# EbookReader_Schematic.net
KiCad netlist of a schematic drawn in EAGLE
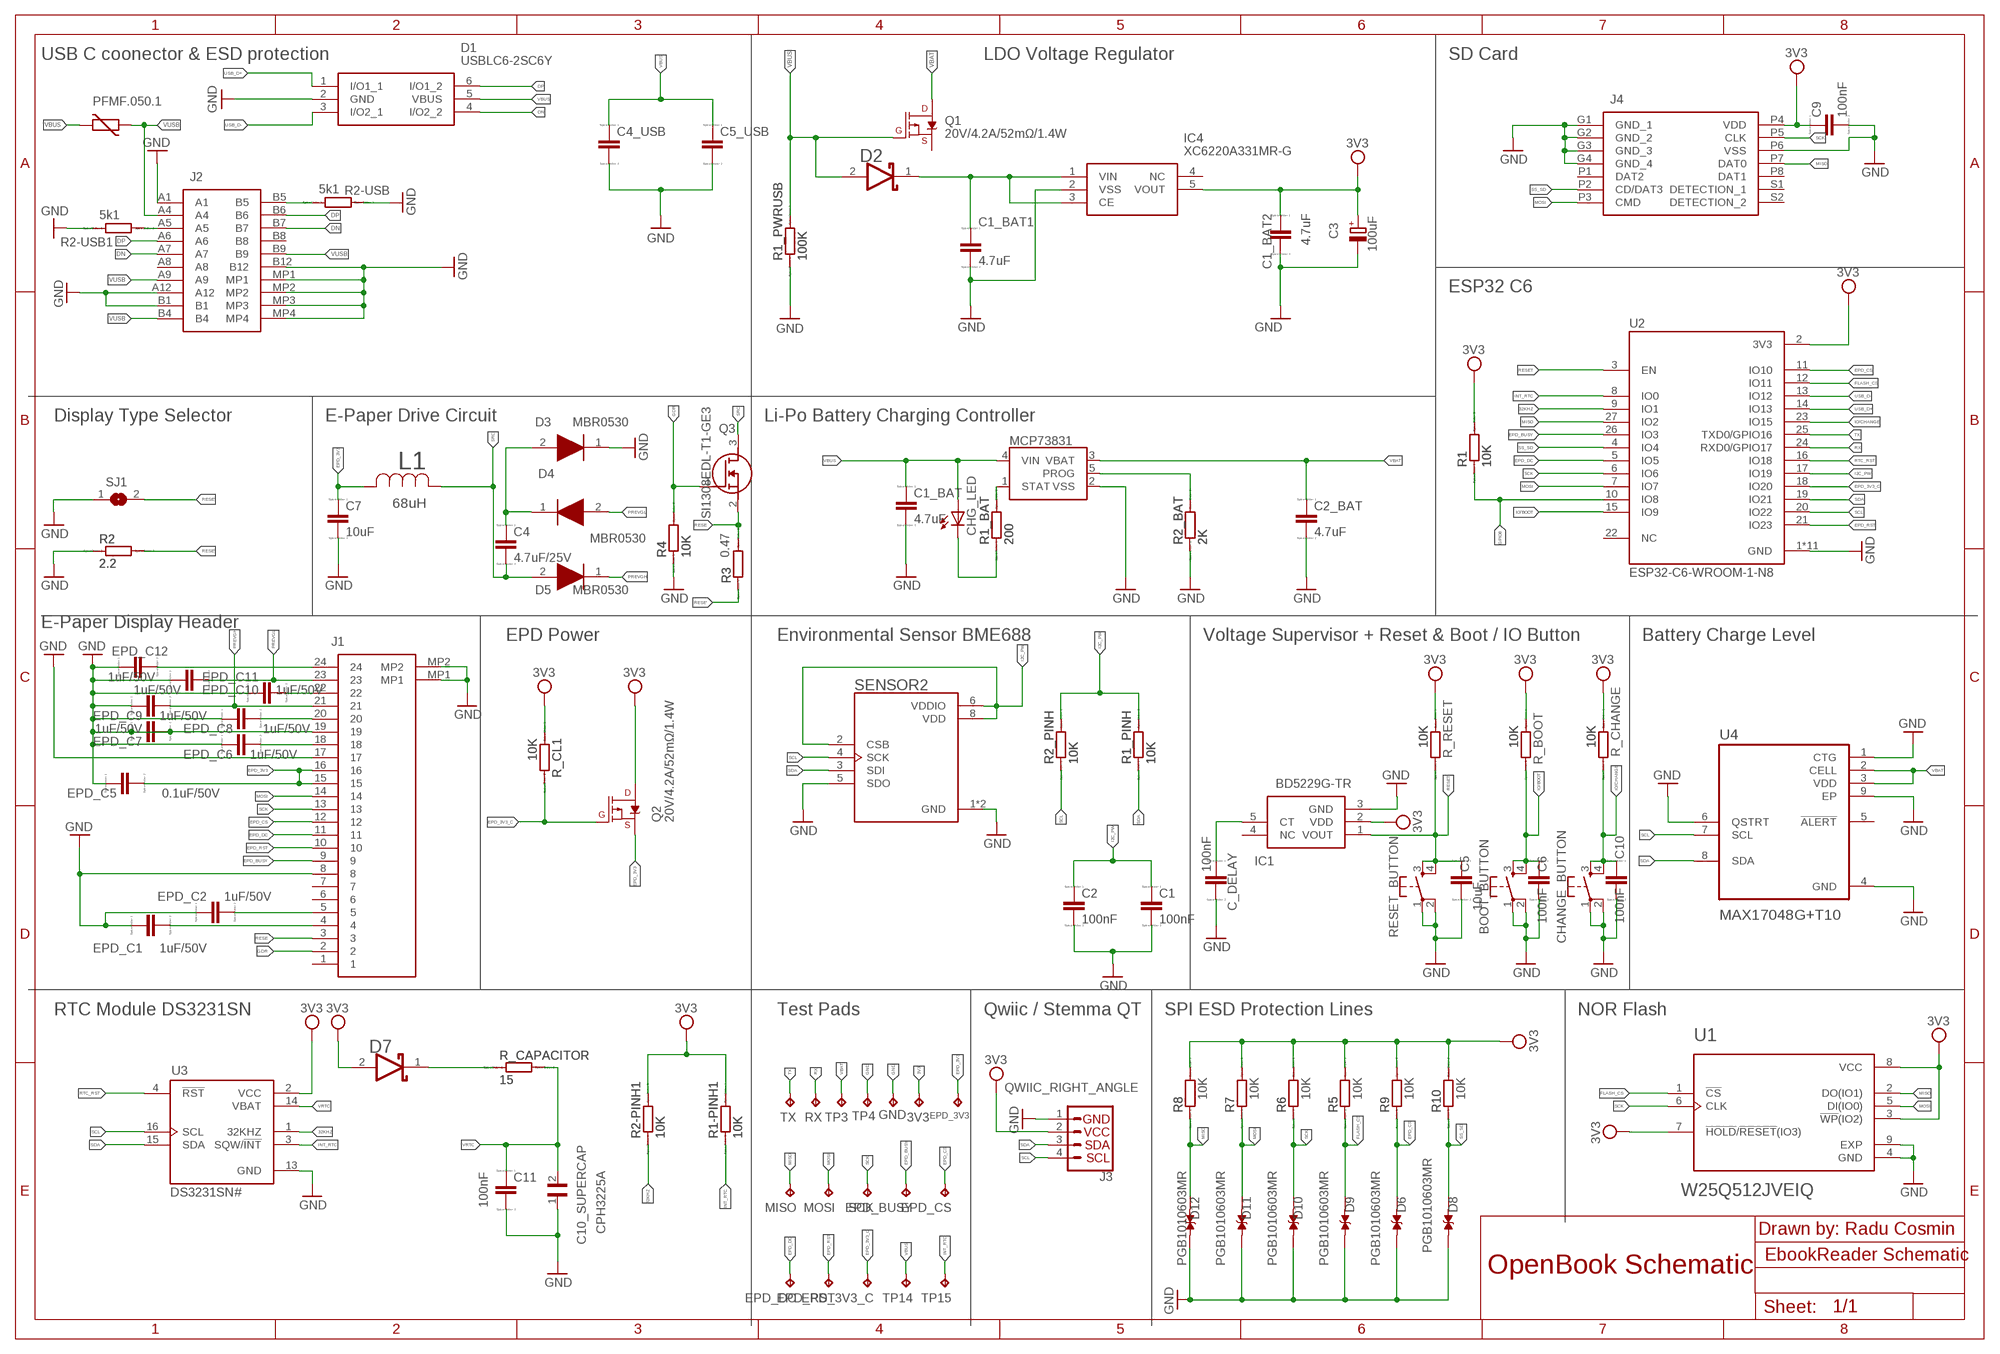
[diagram p0: schematic, sheet 1]

(export (version "E")
  (design (tool "Eeschema 10.0.6"))
  (components
    (comp (ref "3V3")
      (value "TPTP20R")
      (footprint "eagle-import:TP20R")
      (libsource (lib "eagle-import") (part "TPTP20R"))
    )
    (comp (ref "BOOT_BUTTON")
      (value "BUTTON_CUSYOMV1")
      (footprint "eagle-import:MYBUTTON")
      (libsource (lib "eagle-import") (part "BUTTON_CUSYOMV1"))
    )
    (comp (ref "C1")
      (value "100nF")
      (footprint "eagle-import:ESP32_WROVER_EAGLE-LTSPICE_C0402")
      (libsource (lib "eagle-import") (part "ESP32_WROVER_EAGLE-LTSPICE_CC0402"))
    )
    (comp (ref "C1_BAT")
      (value "4.7uF")
      (footprint "eagle-import:ESP32_WROVER_EAGLE-LTSPICE_C0402")
      (libsource (lib "eagle-import") (part "ESP32_WROVER_EAGLE-LTSPICE_CC0402"))
    )
    (comp (ref "C1_BAT1")
      (value "4.7uF")
      (footprint "eagle-import:ESP32_WROVER_EAGLE-LTSPICE_C0402")
      (libsource (lib "eagle-import") (part "ESP32_WROVER_EAGLE-LTSPICE_CC0402"))
    )
    (comp (ref "C1_BAT2")
      (value "4.7uF")
      (footprint "eagle-import:ESP32_WROVER_EAGLE-LTSPICE_C0402")
      (libsource (lib "eagle-import") (part "ESP32_WROVER_EAGLE-LTSPICE_CC0402"))
    )
    (comp (ref "C2")
      (value "100nF")
      (footprint "eagle-import:ESP32_WROVER_EAGLE-LTSPICE_C0402")
      (libsource (lib "eagle-import") (part "ESP32_WROVER_EAGLE-LTSPICE_CC0402"))
    )
    (comp (ref "C2_BAT")
      (value "4.7uF")
      (footprint "eagle-import:ESP32_WROVER_EAGLE-LTSPICE_C0402")
      (libsource (lib "eagle-import") (part "ESP32_WROVER_EAGLE-LTSPICE_CC0402"))
    )
    (comp (ref "C3")
      (value "100uF")
      (footprint "eagle-import:RCL_CT3528")
      (libsource (lib "eagle-import") (part "RCL_CPOL-EUCT3528"))
    )
    (comp (ref "C4")
      (value "4.7uF/25V")
      (footprint "eagle-import:ESP32_WROVER_EAGLE-LTSPICE_C0402")
      (libsource (lib "eagle-import") (part "ESP32_WROVER_EAGLE-LTSPICE_CC0402"))
    )
    (comp (ref "C4_USB")
      (value "ESP32_WROVER_EAGLE-LTSPICE_CC0402")
      (footprint "eagle-import:ESP32_WROVER_EAGLE-LTSPICE_C0402")
      (libsource (lib "eagle-import") (part "ESP32_WROVER_EAGLE-LTSPICE_CC0402"))
    )
    (comp (ref "C5")
      (value "10uF")
      (footprint "eagle-import:ESP32_WROVER_EAGLE-LTSPICE_C0402")
      (libsource (lib "eagle-import") (part "ESP32_WROVER_EAGLE-LTSPICE_CC0402"))
    )
    (comp (ref "C5_USB")
      (value "ESP32_WROVER_EAGLE-LTSPICE_CC0402")
      (footprint "eagle-import:ESP32_WROVER_EAGLE-LTSPICE_C0402")
      (libsource (lib "eagle-import") (part "ESP32_WROVER_EAGLE-LTSPICE_CC0402"))
    )
    (comp (ref "C6")
      (value "100nF")
      (footprint "eagle-import:ESP32_WROVER_EAGLE-LTSPICE_C0402")
      (libsource (lib "eagle-import") (part "ESP32_WROVER_EAGLE-LTSPICE_CC0402"))
    )
    (comp (ref "C7")
      (value "10uF")
      (footprint "eagle-import:ESP32_WROVER_EAGLE-LTSPICE_C0402")
      (libsource (lib "eagle-import") (part "ESP32_WROVER_EAGLE-LTSPICE_CC0402"))
    )
    (comp (ref "C9")
      (value "100nF")
      (footprint "eagle-import:ESP32_WROVER_EAGLE-LTSPICE_C0402")
      (libsource (lib "eagle-import") (part "ESP32_WROVER_EAGLE-LTSPICE_CC0402"))
    )
    (comp (ref "C10")
      (value "100nF")
      (footprint "eagle-import:ESP32_WROVER_EAGLE-LTSPICE_C0402")
      (libsource (lib "eagle-import") (part "ESP32_WROVER_EAGLE-LTSPICE_CC0402"))
    )
    (comp (ref "C10_SUPERCAP")
      (value "CPH3225A")
      (footprint "eagle-import:CAPCP3225X100N")
      (fields (field (name "MF") "Seiko Instruments"))
      (libsource (lib "eagle-import") (part "CPH3225A"))
    )
    (comp (ref "C11")
      (value "100nF")
      (footprint "eagle-import:ESP32_WROVER_EAGLE-LTSPICE_C0402")
      (libsource (lib "eagle-import") (part "ESP32_WROVER_EAGLE-LTSPICE_CC0402"))
    )
    (comp (ref "CHANGE_BUTTON")
      (value "BUTTON_CUSYOMV1")
      (footprint "eagle-import:MYBUTTON")
      (libsource (lib "eagle-import") (part "BUTTON_CUSYOMV1"))
    )
    (comp (ref "CHG_LED")
      (value "ADAFRUIT_LEDCHIP-LED0603")
      (footprint "eagle-import:ADAFRUIT_CHIP-LED0603")
      (libsource (lib "eagle-import") (part "ADAFRUIT_LEDCHIP-LED0603"))
    )
    (comp (ref "C_DELAY")
      (value "100nF")
      (footprint "eagle-import:ESP32_WROVER_EAGLE-LTSPICE_C0402")
      (libsource (lib "eagle-import") (part "ESP32_WROVER_EAGLE-LTSPICE_CC0402"))
    )
    (comp (ref "D1")
      (value "USBLC6-2SC6Y")
      (footprint "eagle-import:SOT95P280X145-6N")
      (fields (field (name "MF") "STMicroelectronics"))
      (libsource (lib "eagle-import") (part "USBLC6-2SC6Y"))
    )
    (comp (ref "D2")
      (value "ESP32_WROVER_AVX---SD0805S020S1R0_AVX_SD0805S020S1R0_0_0AVX_SD0805S020S1R0_0_0")
      (footprint "eagle-import:ESP32_WROVER_AVX---SD0805S020S1R0_AVX_SD0805S020S1R0_0")
      (fields
        (field (name "DIGIKEY_PART_NUMBER") "478-7800-1-ND")
        (field (name "MF") "AVX")
        (field (name "MOUSER_PART_NUMBER") "581-SD0805S020S1R0")
      )
      (libsource (lib "eagle-import") (part "ESP32_WROVER_AVX---SD0805S020S1R0_AVX_SD0805S020S1R0_0_0AVX_SD0805S020S1R0_0_0"))
    )
    (comp (ref "D3")
      (value "MBR0530")
      (footprint "eagle-import:SOD3716X135N")
      (fields (field (name "MF") "ON Semiconductor"))
      (libsource (lib "eagle-import") (part "MBR0530"))
    )
    (comp (ref "D4")
      (value "MBR0530")
      (footprint "eagle-import:SOD3716X135N")
      (fields (field (name "MF") "ON Semiconductor"))
      (libsource (lib "eagle-import") (part "MBR0530"))
    )
    (comp (ref "D5")
      (value "MBR0530")
      (footprint "eagle-import:SOD3716X135N")
      (fields (field (name "MF") "ON Semiconductor"))
      (libsource (lib "eagle-import") (part "MBR0530"))
    )
    (comp (ref "D6")
      (value "PGB1010603MR")
      (footprint "eagle-import:DIOC1608X36N")
      (fields (field (name "MF") "Littelfuse Inc."))
      (libsource (lib "eagle-import") (part "PGB1010603MR"))
    )
    (comp (ref "D7")
      (value "ESP32_WROVER_AVX---SD0805S020S1R0_AVX_SD0805S020S1R0_0_0AVX_SD0805S020S1R0_0_0")
      (footprint "eagle-import:ESP32_WROVER_AVX---SD0805S020S1R0_AVX_SD0805S020S1R0_0")
      (fields
        (field (name "DIGIKEY_PART_NUMBER") "478-7800-1-ND")
        (field (name "MF") "AVX")
        (field (name "MOUSER_PART_NUMBER") "581-SD0805S020S1R0")
      )
      (libsource (lib "eagle-import") (part "ESP32_WROVER_AVX---SD0805S020S1R0_AVX_SD0805S020S1R0_0_0AVX_SD0805S020S1R0_0_0"))
    )
    (comp (ref "D8")
      (value "PGB1010603MR")
      (footprint "eagle-import:DIOC1608X36N")
      (fields (field (name "MF") "Littelfuse Inc."))
      (libsource (lib "eagle-import") (part "PGB1010603MR"))
    )
    (comp (ref "D9")
      (value "PGB1010603MR")
      (footprint "eagle-import:DIOC1608X36N")
      (fields (field (name "MF") "Littelfuse Inc."))
      (libsource (lib "eagle-import") (part "PGB1010603MR"))
    )
    (comp (ref "D10")
      (value "PGB1010603MR")
      (footprint "eagle-import:DIOC1608X36N")
      (fields (field (name "MF") "Littelfuse Inc."))
      (libsource (lib "eagle-import") (part "PGB1010603MR"))
    )
    (comp (ref "D11")
      (value "PGB1010603MR")
      (footprint "eagle-import:DIOC1608X36N")
      (fields (field (name "MF") "Littelfuse Inc."))
      (libsource (lib "eagle-import") (part "PGB1010603MR"))
    )
    (comp (ref "D12")
      (value "PGB1010603MR")
      (footprint "eagle-import:DIOC1608X36N")
      (fields (field (name "MF") "Littelfuse Inc."))
      (libsource (lib "eagle-import") (part "PGB1010603MR"))
    )
    (comp (ref "EPD_3V3")
      (value "TPTP20R")
      (footprint "eagle-import:TP20R")
      (libsource (lib "eagle-import") (part "TPTP20R"))
    )
    (comp (ref "EPD_3V3_C")
      (value "TPTP20R")
      (footprint "eagle-import:TP20R")
      (libsource (lib "eagle-import") (part "TPTP20R"))
    )
    (comp (ref "EPD_BUSY")
      (value "TPTP20R")
      (footprint "eagle-import:TP20R")
      (libsource (lib "eagle-import") (part "TPTP20R"))
    )
    (comp (ref "EPD_C1")
      (value "1uF/50V")
      (footprint "eagle-import:ESP32_WROVER_EAGLE-LTSPICE_C0402")
      (libsource (lib "eagle-import") (part "ESP32_WROVER_EAGLE-LTSPICE_CC0402"))
    )
    (comp (ref "EPD_C2")
      (value "1uF/50V")
      (footprint "eagle-import:ESP32_WROVER_EAGLE-LTSPICE_C0402")
      (libsource (lib "eagle-import") (part "ESP32_WROVER_EAGLE-LTSPICE_CC0402"))
    )
    (comp (ref "EPD_C5")
      (value "0.1uF/50V")
      (footprint "eagle-import:ESP32_WROVER_EAGLE-LTSPICE_C0402")
      (libsource (lib "eagle-import") (part "ESP32_WROVER_EAGLE-LTSPICE_CC0402"))
    )
    (comp (ref "EPD_C6")
      (value "1uF/50V")
      (footprint "eagle-import:ESP32_WROVER_EAGLE-LTSPICE_C0402")
      (libsource (lib "eagle-import") (part "ESP32_WROVER_EAGLE-LTSPICE_CC0402"))
    )
    (comp (ref "EPD_C7")
      (value "1uF/50V")
      (footprint "eagle-import:ESP32_WROVER_EAGLE-LTSPICE_C0402")
      (libsource (lib "eagle-import") (part "ESP32_WROVER_EAGLE-LTSPICE_CC0402"))
    )
    (comp (ref "EPD_C8")
      (value "1uF/50V")
      (footprint "eagle-import:ESP32_WROVER_EAGLE-LTSPICE_C0402")
      (libsource (lib "eagle-import") (part "ESP32_WROVER_EAGLE-LTSPICE_CC0402"))
    )
    (comp (ref "EPD_C9")
      (value "1uF/50V")
      (footprint "eagle-import:ESP32_WROVER_EAGLE-LTSPICE_C0402")
      (libsource (lib "eagle-import") (part "ESP32_WROVER_EAGLE-LTSPICE_CC0402"))
    )
    (comp (ref "EPD_C10")
      (value "1uF/50V")
      (footprint "eagle-import:ESP32_WROVER_EAGLE-LTSPICE_C0402")
      (libsource (lib "eagle-import") (part "ESP32_WROVER_EAGLE-LTSPICE_CC0402"))
    )
    (comp (ref "EPD_C11")
      (value "1uF/50V")
      (footprint "eagle-import:ESP32_WROVER_EAGLE-LTSPICE_C0402")
      (libsource (lib "eagle-import") (part "ESP32_WROVER_EAGLE-LTSPICE_CC0402"))
    )
    (comp (ref "EPD_C12")
      (value "1uF/50V")
      (footprint "eagle-import:ESP32_WROVER_EAGLE-LTSPICE_C0402")
      (libsource (lib "eagle-import") (part "ESP32_WROVER_EAGLE-LTSPICE_CC0402"))
    )
    (comp (ref "EPD_CS")
      (value "TPTP20R")
      (footprint "eagle-import:TP20R")
      (libsource (lib "eagle-import") (part "TPTP20R"))
    )
    (comp (ref "EPD_DC")
      (value "TPTP20R")
      (footprint "eagle-import:TP20R")
      (libsource (lib "eagle-import") (part "TPTP20R"))
    )
    (comp (ref "EPD_RST")
      (value "TPTP20R")
      (footprint "eagle-import:TP20R")
      (libsource (lib "eagle-import") (part "TPTP20R"))
    )
    (comp (ref "GND")
      (value "TPTP20R")
      (footprint "eagle-import:TP20R")
      (libsource (lib "eagle-import") (part "TPTP20R"))
    )
    (comp (ref "IC1")
      (value "BD5229G-TR")
      (footprint "eagle-import:SOT95P280X125-5N")
      (fields (field (name "MOUSER_PART_NUMBER") "755-BD5229G-TR"))
      (libsource (lib "eagle-import") (part "BD5229G-TR"))
    )
    (comp (ref "IC4")
      (value "XC6220A331MR-G")
      (footprint "eagle-import:SOT95P280X120-5N")
      (fields (field (name "MOUSER_PART_NUMBER") "865-XC6220A331MR-G"))
      (libsource (lib "eagle-import") (part "XC6220A331MR-G"))
    )
    (comp (ref "J1")
      (value "FH34SRJ-24S-0.5SH_99_")
      (footprint "eagle-import:FH34SRJ24S05SH99")
      (fields
        (field (name "MANUFACTURER_PART_NUMBER") "FH34SRJ-24S-0.5SH(99)")
        (field (name "MOUSER_PART_NUMBER") "798-FH34SRJ24S05SH99")
      )
      (libsource (lib "eagle-import") (part "FH34SRJ-24S-0.5SH_99_"))
    )
    (comp (ref "J2")
      (value "SAMACSYS_PARTS_USB4110-GF-A")
      (footprint "eagle-import:SAMACSYS_PARTS_USB4110GFA")
      (fields
        (field (name "MANUFACTURER_PART_NUMBER") "USB4110-GF-A")
        (field (name "MOUSER_PART_NUMBER") "640-USB4110-GF-A")
      )
      (libsource (lib "eagle-import") (part "SAMACSYS_PARTS_USB4110-GF-A"))
    )
    (comp (ref "J3")
      (value "QWIIC_RIGHT_ANGLE")
      (footprint "eagle-import:JST04_1MM_RA")
      (libsource (lib "eagle-import") (part "QWIIC_CONNECTORJS-1MM"))
    )
    (comp (ref "J4")
      (value "112A-TAAR-R03_ATTEND")
      (footprint "eagle-import:112ATAARR03ATTEND")
      (fields (field (name "MANUFACTURER_PART_NUMBER") "112A-TAAR-R03 ATTEND"))
      (libsource (lib "eagle-import") (part "112A-TAAR-R03_ATTEND"))
    )
    (comp (ref "L1")
      (value "68uH")
      (footprint "eagle-import:IND_4828-WE-TPC_WRE")
      (fields
        (field (name "MANUFACTURER_PART_NUMBER") "744043680")
        (field (name "COPYRIGHT") "Copyright (C) 2024 Ultra Librarian. All rights reserved.")
      )
      (libsource (lib "eagle-import") (part "744043680IND_4828-WE-TPC_WRE2"))
    )
    (comp (ref "MCP73831")
      (value "ESP32_WROVER_SPARKFUN-IC-POWER_MCP73831")
      (footprint "eagle-import:ESP32_WROVER_SPARKFUN-IC-POWER_SOT23-5")
      (libsource (lib "eagle-import") (part "ESP32_WROVER_SPARKFUN-IC-POWER_MCP73831"))
    )
    (comp (ref "MISO")
      (value "TPTP20R")
      (footprint "eagle-import:TP20R")
      (libsource (lib "eagle-import") (part "TPTP20R"))
    )
    (comp (ref "MOSI")
      (value "TPTP20R")
      (footprint "eagle-import:TP20R")
      (libsource (lib "eagle-import") (part "TPTP20R"))
    )
    (comp (ref "PFMF.050.1")
      (value "ESP32C6_VARISTORCN1812")
      (footprint "eagle-import:ESP32C6_VARISTOR_CT_CN1812")
      (libsource (lib "eagle-import") (part "ESP32C6_VARISTORCN1812"))
    )
    (comp (ref "Q1")
      (value "20V/4.2A/52mΩ/1.4W")
      (footprint "eagle-import:ESP32_WROVER_SPARKFUN-DISCRETESEMI_SOT23-3")
      (libsource (lib "eagle-import") (part "ESP32_WROVER_SPARKFUN-DISCRETESEMI_MOSFET_PCH-DMG2305UX-7"))
    )
    (comp (ref "Q2")
      (value "20V/4.2A/52mΩ/1.4W")
      (footprint "eagle-import:ESP32_WROVER_SPARKFUN-DISCRETESEMI_SOT23-3")
      (libsource (lib "eagle-import") (part "ESP32_WROVER_SPARKFUN-DISCRETESEMI_MOSFET_PCH-DMG2305UX-7"))
    )
    (comp (ref "Q3")
      (value "SI1308EDL-T1-GE3")
      (footprint "eagle-import:SOT65P210X110-3N")
      (fields (field (name "MF") "Vishay Siliconix"))
      (libsource (lib "eagle-import") (part "SI1308EDL-T1-GE3"))
    )
    (comp (ref "R1")
      (value "10K")
      (footprint "eagle-import:ESP32_WROVER_EAGLE-LTSPICE_R0402")
      (libsource (lib "eagle-import") (part "ESP32_WROVER_EAGLE-LTSPICE_RR0402"))
    )
    (comp (ref "R1-PINH1")
      (value "10K")
      (footprint "eagle-import:ESP32_WROVER_EAGLE-LTSPICE_R0402")
      (libsource (lib "eagle-import") (part "ESP32_WROVER_EAGLE-LTSPICE_RR0402"))
    )
    (comp (ref "R1_BAT")
      (value "200")
      (footprint "eagle-import:ESP32_WROVER_EAGLE-LTSPICE_R0402")
      (libsource (lib "eagle-import") (part "ESP32_WROVER_EAGLE-LTSPICE_RR0402"))
    )
    (comp (ref "R1_PINH")
      (value "10K")
      (footprint "eagle-import:ESP32_WROVER_EAGLE-LTSPICE_R0402")
      (libsource (lib "eagle-import") (part "ESP32_WROVER_EAGLE-LTSPICE_RR0402"))
    )
    (comp (ref "R1_PWRUSB")
      (value "100K")
      (footprint "eagle-import:ESP32_WROVER_EAGLE-LTSPICE_R0402")
      (libsource (lib "eagle-import") (part "ESP32_WROVER_EAGLE-LTSPICE_RR0402"))
    )
    (comp (ref "R2")
      (value "2.2")
      (footprint "eagle-import:ESP32_WROVER_EAGLE-LTSPICE_R0402")
      (libsource (lib "eagle-import") (part "ESP32_WROVER_EAGLE-LTSPICE_RR0402"))
    )
    (comp (ref "R2-PINH1")
      (value "10K")
      (footprint "eagle-import:ESP32_WROVER_EAGLE-LTSPICE_R0402")
      (libsource (lib "eagle-import") (part "ESP32_WROVER_EAGLE-LTSPICE_RR0402"))
    )
    (comp (ref "R2-USB")
      (value "5k1")
      (footprint "eagle-import:ESP32_WROVER_EAGLE-LTSPICE_R0402")
      (libsource (lib "eagle-import") (part "ESP32_WROVER_EAGLE-LTSPICE_RR0402"))
    )
    (comp (ref "R2-USB1")
      (value "5k1")
      (footprint "eagle-import:ESP32_WROVER_EAGLE-LTSPICE_R0402")
      (libsource (lib "eagle-import") (part "ESP32_WROVER_EAGLE-LTSPICE_RR0402"))
    )
    (comp (ref "R2_BAT")
      (value "2K")
      (footprint "eagle-import:ESP32_WROVER_EAGLE-LTSPICE_R0402")
      (libsource (lib "eagle-import") (part "ESP32_WROVER_EAGLE-LTSPICE_RR0402"))
    )
    (comp (ref "R2_PINH")
      (value "10K")
      (footprint "eagle-import:ESP32_WROVER_EAGLE-LTSPICE_R0402")
      (libsource (lib "eagle-import") (part "ESP32_WROVER_EAGLE-LTSPICE_RR0402"))
    )
    (comp (ref "R3")
      (value "0.47")
      (footprint "eagle-import:ESP32_WROVER_EAGLE-LTSPICE_R0402")
      (libsource (lib "eagle-import") (part "ESP32_WROVER_EAGLE-LTSPICE_RR0402"))
    )
    (comp (ref "R4")
      (value "10K")
      (footprint "eagle-import:ESP32_WROVER_EAGLE-LTSPICE_R0402")
      (libsource (lib "eagle-import") (part "ESP32_WROVER_EAGLE-LTSPICE_RR0402"))
    )
    (comp (ref "R5")
      (value "10K")
      (footprint "eagle-import:ESP32_WROVER_EAGLE-LTSPICE_R0402")
      (libsource (lib "eagle-import") (part "ESP32_WROVER_EAGLE-LTSPICE_RR0402"))
    )
    (comp (ref "R6")
      (value "10K")
      (footprint "eagle-import:ESP32_WROVER_EAGLE-LTSPICE_R0402")
      (libsource (lib "eagle-import") (part "ESP32_WROVER_EAGLE-LTSPICE_RR0402"))
    )
    (comp (ref "R7")
      (value "10K")
      (footprint "eagle-import:ESP32_WROVER_EAGLE-LTSPICE_R0402")
      (libsource (lib "eagle-import") (part "ESP32_WROVER_EAGLE-LTSPICE_RR0402"))
    )
    (comp (ref "R8")
      (value "10K")
      (footprint "eagle-import:ESP32_WROVER_EAGLE-LTSPICE_R0402")
      (libsource (lib "eagle-import") (part "ESP32_WROVER_EAGLE-LTSPICE_RR0402"))
    )
    (comp (ref "R9")
      (value "10K")
      (footprint "eagle-import:ESP32_WROVER_EAGLE-LTSPICE_R0402")
      (libsource (lib "eagle-import") (part "ESP32_WROVER_EAGLE-LTSPICE_RR0402"))
    )
    (comp (ref "R10")
      (value "10K")
      (footprint "eagle-import:ESP32_WROVER_EAGLE-LTSPICE_R0402")
      (libsource (lib "eagle-import") (part "ESP32_WROVER_EAGLE-LTSPICE_RR0402"))
    )
    (comp (ref "RESET_BUTTON")
      (value "BUTTON_CUSYOMV1")
      (footprint "eagle-import:MYBUTTON")
      (libsource (lib "eagle-import") (part "BUTTON_CUSYOMV1"))
    )
    (comp (ref "RX")
      (value "TPTP20R")
      (footprint "eagle-import:TP20R")
      (libsource (lib "eagle-import") (part "TPTP20R"))
    )
    (comp (ref "R_BOOT")
      (value "10K")
      (footprint "eagle-import:ESP32_WROVER_EAGLE-LTSPICE_R0402")
      (libsource (lib "eagle-import") (part "ESP32_WROVER_EAGLE-LTSPICE_RR0402"))
    )
    (comp (ref "R_CAPACITOR")
      (value "15")
      (footprint "eagle-import:ESP32_WROVER_EAGLE-LTSPICE_R0402")
      (libsource (lib "eagle-import") (part "ESP32_WROVER_EAGLE-LTSPICE_RR0402"))
    )
    (comp (ref "R_CHANGE")
      (value "10K")
      (footprint "eagle-import:ESP32_WROVER_EAGLE-LTSPICE_R0402")
      (libsource (lib "eagle-import") (part "ESP32_WROVER_EAGLE-LTSPICE_RR0402"))
    )
    (comp (ref "R_CL1")
      (value "10K")
      (footprint "eagle-import:ESP32_WROVER_EAGLE-LTSPICE_R0402")
      (libsource (lib "eagle-import") (part "ESP32_WROVER_EAGLE-LTSPICE_RR0402"))
    )
    (comp (ref "R_RESET")
      (value "10K")
      (footprint "eagle-import:ESP32_WROVER_EAGLE-LTSPICE_R0402")
      (libsource (lib "eagle-import") (part "ESP32_WROVER_EAGLE-LTSPICE_RR0402"))
    )
    (comp (ref "SCK")
      (value "TPTP20R")
      (footprint "eagle-import:TP20R")
      (libsource (lib "eagle-import") (part "TPTP20R"))
    )
    (comp (ref "SENSOR2")
      (value "ESP32_WROVER_BME680_BME680")
      (footprint "eagle-import:ESP32_WROVER_BME680_PSON80P300X300X100-8N")
      (fields (field (name "MF") "Bosch Sensortec") (field (name "MP") "BME680"))
      (libsource (lib "eagle-import") (part "ESP32_WROVER_BME680_BME680"))
    )
    (comp (ref "SJ1") (value "SJ") (footprint "eagle-import:SJ") (libsource (lib "eagle-import") (part "SJ")))
    (comp (ref "TP3")
      (value "TPTP20R")
      (footprint "eagle-import:TP20R")
      (libsource (lib "eagle-import") (part "TPTP20R"))
    )
    (comp (ref "TP4")
      (value "TPTP20R")
      (footprint "eagle-import:TP20R")
      (libsource (lib "eagle-import") (part "TPTP20R"))
    )
    (comp (ref "TP14")
      (value "TPTP20R")
      (footprint "eagle-import:TP20R")
      (libsource (lib "eagle-import") (part "TPTP20R"))
    )
    (comp (ref "TP15")
      (value "TPTP20R")
      (footprint "eagle-import:TP20R")
      (libsource (lib "eagle-import") (part "TPTP20R"))
    )
    (comp (ref "TX")
      (value "TPTP20R")
      (footprint "eagle-import:TP20R")
      (libsource (lib "eagle-import") (part "TPTP20R"))
    )
    (comp (ref "U1")
      (value "W25Q512JVEIQ")
      (footprint "eagle-import:SON127P600X800X80-9N")
      (fields (field (name "MF") "Winbond Electronics"))
      (libsource (lib "eagle-import") (part "W25Q512JVEIQ"))
    )
    (comp (ref "U2")
      (value "ESP32-C6-WROOM-1-N8")
      (footprint "eagle-import:XCVR_ESP32-C6-WROOM-1-N8")
      (fields (field (name "MF") "Espressif Systems"))
      (libsource (lib "eagle-import") (part "ESP32-C6-WROOM-1-N8"))
    )
    (comp (ref "U3")
      (value "DS3231SN#")
      (footprint "eagle-import:SOIC127P1032X265-16N")
      (fields (field (name "MF") "Analog Devices"))
      (libsource (lib "eagle-import") (part "DS3231SN#"))
    )
    (comp (ref "U4")
      (value "MAX17048G+T10")
      (footprint "eagle-import:SON50P200X200X80-9N")
      (fields (field (name "MF") "Analog Devices"))
      (libsource (lib "eagle-import") (part "MAX17048G+T10"))
    )
  )
  (nets
    (net (code "1") (name "3V3") (class "Default")
      (node (ref "3V3") (pin "TP") (pinfunction "TP_TP") (pintype "input"))
      (node (ref "C1_BAT2") (pin "1") (pinfunction "1_1") (pintype "passive"))
      (node (ref "C3") (pin "+") (pinfunction "+_+") (pintype "passive"))
      (node (ref "C9") (pin "1") (pinfunction "1_1") (pintype "passive"))
      (node (ref "D7") (pin "2") (pinfunction "ANODE_2") (pintype "bidirectional"))
      (node (ref "IC1") (pin "2") (pinfunction "VDD_2") (pintype "bidirectional"))
      (node (ref "IC4") (pin "5") (pinfunction "VOUT_5") (pintype "bidirectional"))
      (node (ref "J3") (pin "2") (pinfunction "2_2") (pintype "power_in"))
      (node (ref "J4") (pin "P4") (pinfunction "VDD_P4") (pintype "bidirectional"))
      (node (ref "Q2") (pin "3") (pinfunction "D_3") (pintype "bidirectional"))
      (node (ref "R1") (pin "2") (pinfunction "2_2") (pintype "passive"))
      (node (ref "R1-PINH1") (pin "2") (pinfunction "2_2") (pintype "passive"))
      (node (ref "R10") (pin "2") (pinfunction "2_2") (pintype "passive"))
      (node (ref "R2-PINH1") (pin "2") (pinfunction "2_2") (pintype "passive"))
      (node (ref "R5") (pin "2") (pinfunction "2_2") (pintype "passive"))
      (node (ref "R6") (pin "2") (pinfunction "2_2") (pintype "passive"))
      (node (ref "R7") (pin "2") (pinfunction "2_2") (pintype "passive"))
      (node (ref "R8") (pin "2") (pinfunction "2_2") (pintype "passive"))
      (node (ref "R9") (pin "2") (pinfunction "2_2") (pintype "passive"))
      (node (ref "R_BOOT") (pin "1") (pinfunction "1_1") (pintype "passive"))
      (node (ref "R_CHANGE") (pin "1") (pinfunction "1_1") (pintype "passive"))
      (node (ref "R_CL1") (pin "1") (pinfunction "1_1") (pintype "passive"))
      (node (ref "R_RESET") (pin "1") (pinfunction "1_1") (pintype "passive"))
      (node (ref "U1") (pin "3") (pinfunction "~{WP}(IO2)_3") (pintype "bidirectional"))
      (node (ref "U1") (pin "7") (pinfunction "~{HOLD}/~{RESET}(IO3)_7") (pintype "bidirectional"))
      (node (ref "U1") (pin "8") (pinfunction "VCC_8") (pintype "power_in"))
      (node (ref "U2") (pin "2") (pinfunction "3V3_2") (pintype "power_in"))
      (node (ref "U3") (pin "2") (pinfunction "VCC_2") (pintype "power_in"))
    )
    (net (code "2") (name "32KHZ") (class "Default")
      (node (ref "R2-PINH1") (pin "1") (pinfunction "1_1") (pintype "passive"))
      (node (ref "U2") (pin "9") (pinfunction "IO1_9") (pintype "bidirectional"))
      (node (ref "U3") (pin "1") (pinfunction "32KHZ_1") (pintype "output"))
    )
    (net (code "3") (name "DN") (class "Default")
      (node (ref "D1") (pin "4") (pinfunction "I/O2_2_4") (pintype "bidirectional"))
      (node (ref "J2") (pin "A7") (pinfunction "A7_A7") (pintype "bidirectional"))
      (node (ref "J2") (pin "B7") (pinfunction "B7_B7") (pintype "bidirectional"))
    )
    (net (code "4") (name "DP") (class "Default")
      (node (ref "D1") (pin "6") (pinfunction "I/O1_2_6") (pintype "bidirectional"))
      (node (ref "J2") (pin "A6") (pinfunction "A6_A6") (pintype "bidirectional"))
      (node (ref "J2") (pin "B6") (pinfunction "B6_B6") (pintype "bidirectional"))
    )
    (net (code "5") (name "EPD_3V3") (class "Default")
      (node (ref "C7") (pin "1") (pinfunction "1_1") (pintype "passive"))
      (node (ref "EPD_3V3") (pin "TP") (pinfunction "TP_TP") (pintype "input"))
      (node (ref "EPD_C5") (pin "2") (pinfunction "2_2") (pintype "passive"))
      (node (ref "J1") (pin "15") (pinfunction "15_15") (pintype "bidirectional"))
      (node (ref "J1") (pin "16") (pinfunction "16_16") (pintype "bidirectional"))
      (node (ref "L1") (pin "2") (pinfunction "2_2") (pintype "passive"))
      (node (ref "Q2") (pin "2") (pinfunction "S_2") (pintype "bidirectional"))
    )
    (net (code "6") (name "EPD_3V3_C") (class "Default")
      (node (ref "EPD_3V3_C") (pin "TP") (pinfunction "TP_TP") (pintype "input"))
      (node (ref "Q2") (pin "1") (pinfunction "G_1") (pintype "bidirectional"))
      (node (ref "R_CL1") (pin "2") (pinfunction "2_2") (pintype "passive"))
      (node (ref "U2") (pin "18") (pinfunction "IO20_18") (pintype "bidirectional"))
    )
    (net (code "7") (name "EPD_BUSY") (class "Default")
      (node (ref "EPD_BUSY") (pin "TP") (pinfunction "TP_TP") (pintype "input"))
      (node (ref "J1") (pin "9") (pinfunction "9_9") (pintype "bidirectional"))
      (node (ref "U2") (pin "26") (pinfunction "IO3_26") (pintype "bidirectional"))
    )
    (net (code "8") (name "EPD_CS") (class "Default")
      (node (ref "D6") (pin "1") (pinfunction "1_1") (pintype "passive"))
      (node (ref "EPD_CS") (pin "TP") (pinfunction "TP_TP") (pintype "input"))
      (node (ref "J1") (pin "12") (pinfunction "12_12") (pintype "bidirectional"))
      (node (ref "R9") (pin "1") (pinfunction "1_1") (pintype "passive"))
      (node (ref "U2") (pin "11") (pinfunction "IO10_11") (pintype "bidirectional"))
    )
    (net (code "9") (name "EPD_DC") (class "Default")
      (node (ref "EPD_DC") (pin "TP") (pinfunction "TP_TP") (pintype "input"))
      (node (ref "J1") (pin "11") (pinfunction "11_11") (pintype "bidirectional"))
      (node (ref "U2") (pin "5") (pinfunction "IO5_5") (pintype "bidirectional"))
    )
    (net (code "10") (name "EPD_RST") (class "Default")
      (node (ref "EPD_RST") (pin "TP") (pinfunction "TP_TP") (pintype "input"))
      (node (ref "J1") (pin "10") (pinfunction "10_10") (pintype "bidirectional"))
      (node (ref "U2") (pin "21") (pinfunction "IO23_21") (pintype "bidirectional"))
    )
    (net (code "11") (name "FLASH_CS") (class "Default")
      (node (ref "D9") (pin "1") (pinfunction "1_1") (pintype "passive"))
      (node (ref "R5") (pin "1") (pinfunction "1_1") (pintype "passive"))
      (node (ref "U1") (pin "1") (pinfunction "~{CS}_1") (pintype "input"))
      (node (ref "U2") (pin "12") (pinfunction "IO11_12") (pintype "bidirectional"))
    )
    (net (code "12") (name "GDR") (class "Default")
      (node (ref "J1") (pin "2") (pinfunction "2_2") (pintype "bidirectional"))
      (node (ref "Q3") (pin "1") (pinfunction "G_1") (pintype "bidirectional"))
      (node (ref "R4") (pin "2") (pinfunction "2_2") (pintype "passive"))
    )
    (net (code "13") (name "GND") (class "Default")
      (node (ref "BOOT_BUTTON") (pin "1") (pinfunction "1_1") (pintype "passive"))
      (node (ref "BOOT_BUTTON") (pin "2") (pinfunction "2_2") (pintype "passive"))
      (node (ref "C1") (pin "2") (pinfunction "2_2") (pintype "passive"))
      (node (ref "C10") (pin "2") (pinfunction "2_2") (pintype "passive"))
      (node (ref "C10_SUPERCAP") (pin "1") (pinfunction "1_1") (pintype "passive"))
      (node (ref "C11") (pin "2") (pinfunction "2_2") (pintype "passive"))
      (node (ref "C1_BAT") (pin "2") (pinfunction "2_2") (pintype "passive"))
      (node (ref "C1_BAT1") (pin "2") (pinfunction "2_2") (pintype "passive"))
      (node (ref "C1_BAT2") (pin "2") (pinfunction "2_2") (pintype "passive"))
      (node (ref "C2") (pin "2") (pinfunction "2_2") (pintype "passive"))
      (node (ref "C2_BAT") (pin "2") (pinfunction "2_2") (pintype "passive"))
      (node (ref "C3") (pin "-") (pinfunction "-_-") (pintype "passive"))
      (node (ref "C4_USB") (pin "2") (pinfunction "2_2") (pintype "passive"))
      (node (ref "C5") (pin "2") (pinfunction "2_2") (pintype "passive"))
      (node (ref "C5_USB") (pin "2") (pinfunction "2_2") (pintype "passive"))
      (node (ref "C6") (pin "2") (pinfunction "2_2") (pintype "passive"))
      (node (ref "C7") (pin "2") (pinfunction "2_2") (pintype "passive"))
      (node (ref "C9") (pin "2") (pinfunction "2_2") (pintype "passive"))
      (node (ref "CHANGE_BUTTON") (pin "1") (pinfunction "1_1") (pintype "passive"))
      (node (ref "CHANGE_BUTTON") (pin "2") (pinfunction "2_2") (pintype "passive"))
      (node (ref "C_DELAY") (pin "2") (pinfunction "2_2") (pintype "passive"))
      (node (ref "D1") (pin "2") (pinfunction "GND_2") (pintype "bidirectional"))
      (node (ref "D10") (pin "2") (pinfunction "2_2") (pintype "passive"))
      (node (ref "D11") (pin "2") (pinfunction "2_2") (pintype "passive"))
      (node (ref "D12") (pin "2") (pinfunction "2_2") (pintype "passive"))
      (node (ref "D3") (pin "1") (pinfunction "K_1") (pintype "bidirectional"))
      (node (ref "D6") (pin "2") (pinfunction "2_2") (pintype "passive"))
      (node (ref "D8") (pin "2") (pinfunction "2_2") (pintype "passive"))
      (node (ref "D9") (pin "2") (pinfunction "2_2") (pintype "passive"))
      (node (ref "EPD_C1") (pin "1") (pinfunction "1_1") (pintype "passive"))
      (node (ref "EPD_C10") (pin "1") (pinfunction "1_1") (pintype "passive"))
      (node (ref "EPD_C11") (pin "1") (pinfunction "1_1") (pintype "passive"))
      (node (ref "EPD_C12") (pin "1") (pinfunction "1_1") (pintype "passive"))
      (node (ref "EPD_C2") (pin "1") (pinfunction "1_1") (pintype "passive"))
      (node (ref "EPD_C5") (pin "1") (pinfunction "1_1") (pintype "passive"))
      (node (ref "EPD_C6") (pin "1") (pinfunction "1_1") (pintype "passive"))
      (node (ref "EPD_C7") (pin "1") (pinfunction "1_1") (pintype "passive"))
      (node (ref "EPD_C7") (pin "2") (pinfunction "2_2") (pintype "passive"))
      (node (ref "EPD_C8") (pin "1") (pinfunction "1_1") (pintype "passive"))
      (node (ref "EPD_C9") (pin "1") (pinfunction "1_1") (pintype "passive"))
      (node (ref "GND") (pin "TP") (pinfunction "TP_TP") (pintype "input"))
      (node (ref "IC1") (pin "3") (pinfunction "GND_3") (pintype "bidirectional"))
      (node (ref "IC4") (pin "2") (pinfunction "VSS_2") (pintype "bidirectional"))
      (node (ref "J1") (pin "17") (pinfunction "17_17") (pintype "bidirectional"))
      (node (ref "J1") (pin "19") (pinfunction "19_19") (pintype "bidirectional"))
      (node (ref "J1") (pin "8") (pinfunction "8_8") (pintype "bidirectional"))
      (node (ref "J1") (pin "MP1") (pinfunction "MP1_MP1") (pintype "bidirectional"))
      (node (ref "J1") (pin "MP2") (pinfunction "MP2_MP2") (pintype "bidirectional"))
      (node (ref "J2") (pin "A1") (pinfunction "A1_A1") (pintype "bidirectional"))
      (node (ref "J2") (pin "A12") (pinfunction "A12_A12") (pintype "bidirectional"))
      (node (ref "J2") (pin "B1") (pinfunction "B1_B1") (pintype "bidirectional"))
      (node (ref "J2") (pin "B12") (pinfunction "B12_B12") (pintype "bidirectional"))
      (node (ref "J2") (pin "MP1") (pinfunction "MP1_MP1") (pintype "bidirectional"))
      (node (ref "J2") (pin "MP2") (pinfunction "MP2_MP2") (pintype "bidirectional"))
      (node (ref "J2") (pin "MP3") (pinfunction "MP3_MP3") (pintype "bidirectional"))
      (node (ref "J2") (pin "MP4") (pinfunction "MP4_MP4") (pintype "bidirectional"))
      (node (ref "J3") (pin "1") (pinfunction "1_1") (pintype "power_in"))
      (node (ref "J4") (pin "G1") (pinfunction "GND_1_G1") (pintype "bidirectional"))
      (node (ref "J4") (pin "G2") (pinfunction "GND_2_G2") (pintype "bidirectional"))
      (node (ref "J4") (pin "G3") (pinfunction "GND_3_G3") (pintype "bidirectional"))
      (node (ref "J4") (pin "G4") (pinfunction "GND_4_G4") (pintype "bidirectional"))
      (node (ref "J4") (pin "P6") (pinfunction "VSS_P6") (pintype "bidirectional"))
      (node (ref "MCP73831") (pin "2") (pinfunction "VSS_2") (pintype "power_in"))
      (node (ref "R1_PWRUSB") (pin "1") (pinfunction "1_1") (pintype "passive"))
      (node (ref "R2") (pin "1") (pinfunction "1_1") (pintype "passive"))
      (node (ref "R2-USB") (pin "2") (pinfunction "2_2") (pintype "passive"))
      (node (ref "R2-USB1") (pin "1") (pinfunction "1_1") (pintype "passive"))
      (node (ref "R2_BAT") (pin "1") (pinfunction "1_1") (pintype "passive"))
      (node (ref "R4") (pin "1") (pinfunction "1_1") (pintype "passive"))
      (node (ref "RESET_BUTTON") (pin "1") (pinfunction "1_1") (pintype "passive"))
      (node (ref "RESET_BUTTON") (pin "2") (pinfunction "2_2") (pintype "passive"))
      (node (ref "SENSOR2") (pin "1") (pinfunction "GND_1") (pintype "power_in"))
      (node (ref "SENSOR2") (pin "5") (pinfunction "SDO_5") (pintype "bidirectional"))
      (node (ref "SENSOR2") (pin "7") (pinfunction "GND_7") (pintype "power_in"))
      (node (ref "SJ1") (pin "1") (pinfunction "1_1") (pintype "passive"))
      (node (ref "TP4") (pin "TP") (pinfunction "TP_TP") (pintype "input"))
      (node (ref "U1") (pin "4") (pinfunction "GND_4") (pintype "power_in"))
      (node (ref "U1") (pin "9") (pinfunction "EXP_9") (pintype "passive"))
      (node (ref "U2") (pin "1") (pinfunction "GND_1") (pintype "power_in"))
      (node (ref "U2") (pin "28") (pinfunction "GND_28") (pintype "power_in"))
      (node (ref "U2") (pin "29_1") (pinfunction "GND_29_1") (pintype "power_in"))
      (node (ref "U2") (pin "29_2") (pinfunction "GND_29_2") (pintype "power_in"))
      (node (ref "U2") (pin "29_3") (pinfunction "GND_29_3") (pintype "power_in"))
      (node (ref "U2") (pin "29_4") (pinfunction "GND_29_4") (pintype "power_in"))
      (node (ref "U2") (pin "29_5") (pinfunction "GND_29_5") (pintype "power_in"))
      (node (ref "U2") (pin "29_6") (pinfunction "GND_29_6") (pintype "power_in"))
      (node (ref "U2") (pin "29_7") (pinfunction "GND_29_7") (pintype "power_in"))
      (node (ref "U2") (pin "29_8") (pinfunction "GND_29_8") (pintype "power_in"))
      (node (ref "U2") (pin "29_9") (pinfunction "GND_29_9") (pintype "power_in"))
      (node (ref "U3") (pin "13") (pinfunction "GND_13") (pintype "power_in"))
      (node (ref "U4") (pin "1") (pinfunction "CTG_1") (pintype "power_in"))
      (node (ref "U4") (pin "4") (pinfunction "GND_4") (pintype "power_in"))
      (node (ref "U4") (pin "6") (pinfunction "QSTRT_6") (pintype "input"))
      (node (ref "U4") (pin "9") (pinfunction "EP_9") (pintype "power_in"))
    )
    (net (code "14") (name "GPIO8") (class "Default")
      (node (ref "R1") (pin "1") (pinfunction "1_1") (pintype "passive"))
      (node (ref "U2") (pin "10") (pinfunction "IO8_10") (pintype "bidirectional"))
    )
    (net (code "15") (name "I2C_PW") (class "Default")
      (node (ref "C1") (pin "1") (pinfunction "1_1") (pintype "passive"))
      (node (ref "C2") (pin "1") (pinfunction "1_1") (pintype "passive"))
      (node (ref "R1_PINH") (pin "2") (pinfunction "2_2") (pintype "passive"))
      (node (ref "R2_PINH") (pin "2") (pinfunction "2_2") (pintype "passive"))
      (node (ref "SENSOR2") (pin "2") (pinfunction "CSB_2") (pintype "input"))
      (node (ref "SENSOR2") (pin "6") (pinfunction "VDDIO_6") (pintype "power_in"))
      (node (ref "SENSOR2") (pin "8") (pinfunction "VDD_8") (pintype "power_in"))
      (node (ref "U2") (pin "17") (pinfunction "IO19_17") (pintype "bidirectional"))
    )
    (net (code "16") (name "INT_RTC") (class "Default")
      (node (ref "R1-PINH1") (pin "1") (pinfunction "1_1") (pintype "passive"))
      (node (ref "TP15") (pin "TP") (pinfunction "TP_TP") (pintype "input"))
      (node (ref "U2") (pin "8") (pinfunction "IO0_8") (pintype "bidirectional"))
      (node (ref "U3") (pin "3") (pinfunction "SQW/~{INT}_3") (pintype "output"))
    )
    (net (code "17") (name "IO{slash}BOOT") (class "Default")
      (node (ref "BOOT_BUTTON") (pin "3") (pinfunction "3_3") (pintype "passive"))
      (node (ref "BOOT_BUTTON") (pin "4") (pinfunction "4_4") (pintype "passive"))
      (node (ref "C6") (pin "1") (pinfunction "1_1") (pintype "passive"))
      (node (ref "R_BOOT") (pin "2") (pinfunction "2_2") (pintype "passive"))
      (node (ref "U2") (pin "15") (pinfunction "IO9_15") (pintype "bidirectional"))
    )
    (net (code "18") (name "IO{slash}CHANGE") (class "Default")
      (node (ref "C10") (pin "1") (pinfunction "1_1") (pintype "passive"))
      (node (ref "CHANGE_BUTTON") (pin "3") (pinfunction "3_3") (pintype "passive"))
      (node (ref "CHANGE_BUTTON") (pin "4") (pinfunction "4_4") (pintype "passive"))
      (node (ref "R_CHANGE") (pin "2") (pinfunction "2_2") (pintype "passive"))
      (node (ref "U2") (pin "23") (pinfunction "IO15_23") (pintype "bidirectional"))
    )
    (net (code "19") (name "MISO") (class "Default")
      (node (ref "D12") (pin "1") (pinfunction "1_1") (pintype "passive"))
      (node (ref "J4") (pin "P7") (pinfunction "DAT0_P7") (pintype "bidirectional"))
      (node (ref "MISO") (pin "TP") (pinfunction "TP_TP") (pintype "input"))
      (node (ref "R8") (pin "1") (pinfunction "1_1") (pintype "passive"))
      (node (ref "U1") (pin "2") (pinfunction "DO(IO1)_2") (pintype "bidirectional"))
      (node (ref "U2") (pin "27") (pinfunction "IO2_27") (pintype "bidirectional"))
    )
    (net (code "20") (name "MOSI") (class "Default")
      (node (ref "D11") (pin "1") (pinfunction "1_1") (pintype "passive"))
      (node (ref "J1") (pin "14") (pinfunction "14_14") (pintype "bidirectional"))
      (node (ref "J4") (pin "P3") (pinfunction "CMD_P3") (pintype "bidirectional"))
      (node (ref "MOSI") (pin "TP") (pinfunction "TP_TP") (pintype "input"))
      (node (ref "R7") (pin "1") (pinfunction "1_1") (pintype "passive"))
      (node (ref "U1") (pin "5") (pinfunction "DI(IO0)_5") (pintype "bidirectional"))
      (node (ref "U2") (pin "7") (pinfunction "IO7_7") (pintype "bidirectional"))
    )
    (net (code "21") (name "Net-(CHG_LED-PadC)") (class "Default")
      (node (ref "CHG_LED") (pin "C") (pinfunction "C_C") (pintype "passive"))
      (node (ref "R1_BAT") (pin "1") (pinfunction "1_1") (pintype "passive"))
    )
    (net (code "22") (name "Net-(D2-CATHODE)") (class "Default")
      (node (ref "C1_BAT1") (pin "1") (pinfunction "1_1") (pintype "passive"))
      (node (ref "D2") (pin "1") (pinfunction "CATHODE_1") (pintype "bidirectional"))
      (node (ref "IC4") (pin "1") (pinfunction "VIN_1") (pintype "bidirectional"))
      (node (ref "IC4") (pin "3") (pinfunction "CE_3") (pintype "bidirectional"))
    )
    (net (code "23") (name "Net-(D3-A)") (class "Default")
      (node (ref "C4") (pin "1") (pinfunction "1_1") (pintype "passive"))
      (node (ref "D3") (pin "2") (pinfunction "A_2") (pintype "bidirectional"))
      (node (ref "D4") (pin "1") (pinfunction "K_1") (pintype "bidirectional"))
    )
    (net (code "24") (name "Net-(D7-CATHODE)") (class "Default")
      (node (ref "D7") (pin "1") (pinfunction "CATHODE_1") (pintype "bidirectional"))
      (node (ref "R_CAPACITOR") (pin "1") (pinfunction "1_1") (pintype "passive"))
    )
    (net (code "25") (name "Net-(EPD_C1-Pad2)") (class "Default")
      (node (ref "EPD_C1") (pin "2") (pinfunction "2_2") (pintype "passive"))
      (node (ref "J1") (pin "4") (pinfunction "4_4") (pintype "bidirectional"))
    )
    (net (code "26") (name "Net-(EPD_C2-Pad2)") (class "Default")
      (node (ref "EPD_C2") (pin "2") (pinfunction "2_2") (pintype "passive"))
      (node (ref "J1") (pin "5") (pinfunction "5_5") (pintype "bidirectional"))
    )
    (net (code "27") (name "Net-(EPD_C6-Pad2)") (class "Default")
      (node (ref "EPD_C6") (pin "2") (pinfunction "2_2") (pintype "passive"))
      (node (ref "J1") (pin "18") (pinfunction "18_18") (pintype "bidirectional"))
    )
    (net (code "28") (name "Net-(EPD_C8-Pad2)") (class "Default")
      (node (ref "EPD_C8") (pin "2") (pinfunction "2_2") (pintype "passive"))
      (node (ref "J1") (pin "20") (pinfunction "20_20") (pintype "bidirectional"))
    )
    (net (code "29") (name "Net-(EPD_C10-Pad2)") (class "Default")
      (node (ref "EPD_C10") (pin "2") (pinfunction "2_2") (pintype "passive"))
      (node (ref "J1") (pin "22") (pinfunction "22_22") (pintype "bidirectional"))
    )
    (net (code "30") (name "Net-(EPD_C12-Pad2)") (class "Default")
      (node (ref "EPD_C12") (pin "2") (pinfunction "2_2") (pintype "passive"))
      (node (ref "J1") (pin "24") (pinfunction "24_24") (pintype "bidirectional"))
    )
    (net (code "31") (name "Net-(IC1-CT)") (class "Default")
      (node (ref "C_DELAY") (pin "1") (pinfunction "1_1") (pintype "passive"))
      (node (ref "IC1") (pin "5") (pinfunction "CT_5") (pintype "bidirectional"))
    )
    (net (code "32") (name "Net-(J2-PadA5)") (class "Default")
      (node (ref "J2") (pin "A5") (pinfunction "A5_A5") (pintype "bidirectional"))
      (node (ref "R2-USB1") (pin "2") (pinfunction "2_2") (pintype "passive"))
    )
    (net (code "33") (name "Net-(J2-PadB5)") (class "Default")
      (node (ref "J2") (pin "B5") (pinfunction "B5_B5") (pintype "bidirectional"))
      (node (ref "R2-USB") (pin "1") (pinfunction "1_1") (pintype "passive"))
    )
    (net (code "34") (name "Net-(MCP73831-PROG)") (class "Default")
      (node (ref "MCP73831") (pin "5") (pinfunction "PROG_5") (pintype "input"))
      (node (ref "R2_BAT") (pin "2") (pinfunction "2_2") (pintype "passive"))
    )
    (net (code "35") (name "Net-(MCP73831-STAT)") (class "Default")
      (node (ref "MCP73831") (pin "1") (pinfunction "STAT_1") (pintype "output"))
      (node (ref "R1_BAT") (pin "2") (pinfunction "2_2") (pintype "passive"))
    )
    (net (code "36") (name "PREVGH") (class "Default")
      (node (ref "D5") (pin "1") (pinfunction "K_1") (pintype "bidirectional"))
      (node (ref "EPD_C9") (pin "2") (pinfunction "2_2") (pintype "passive"))
      (node (ref "J1") (pin "21") (pinfunction "21_21") (pintype "bidirectional"))
    )
    (net (code "37") (name "PREVGL") (class "Default")
      (node (ref "D4") (pin "2") (pinfunction "A_2") (pintype "bidirectional"))
      (node (ref "EPD_C11") (pin "2") (pinfunction "2_2") (pintype "passive"))
      (node (ref "J1") (pin "23") (pinfunction "23_23") (pintype "bidirectional"))
    )
    (net (code "38") (name "RESE") (class "Default")
      (node (ref "J1") (pin "3") (pinfunction "3_3") (pintype "bidirectional"))
      (node (ref "Q3") (pin "2") (pinfunction "S_2") (pintype "bidirectional"))
      (node (ref "R3") (pin "2") (pinfunction "2_2") (pintype "passive"))
    )
    (net (code "39") (name "RESE'") (class "Default")
      (node (ref "R2") (pin "2") (pinfunction "2_2") (pintype "passive"))
      (node (ref "R3") (pin "1") (pinfunction "1_1") (pintype "passive"))
      (node (ref "SJ1") (pin "2") (pinfunction "2_2") (pintype "passive"))
    )
    (net (code "40") (name "RESET") (class "Default")
      (node (ref "C5") (pin "1") (pinfunction "1_1") (pintype "passive"))
      (node (ref "IC1") (pin "1") (pinfunction "VOUT_1") (pintype "bidirectional"))
      (node (ref "RESET_BUTTON") (pin "3") (pinfunction "3_3") (pintype "passive"))
      (node (ref "RESET_BUTTON") (pin "4") (pinfunction "4_4") (pintype "passive"))
      (node (ref "R_RESET") (pin "2") (pinfunction "2_2") (pintype "passive"))
      (node (ref "U2") (pin "3") (pinfunction "EN_3") (pintype "input"))
    )
    (net (code "41") (name "RTC_RST") (class "Default")
      (node (ref "U2") (pin "16") (pinfunction "IO18_16") (pintype "bidirectional"))
      (node (ref "U3") (pin "4") (pinfunction "~{RST}_4") (pintype "input"))
    )
    (net (code "42") (name "RX") (class "Default")
      (node (ref "RX") (pin "TP") (pinfunction "TP_TP") (pintype "input"))
      (node (ref "U2") (pin "24") (pinfunction "RXD0/GPIO17_24") (pintype "bidirectional"))
    )
    (net (code "43") (name "SCK") (class "Default")
      (node (ref "D10") (pin "1") (pinfunction "1_1") (pintype "passive"))
      (node (ref "J1") (pin "13") (pinfunction "13_13") (pintype "bidirectional"))
      (node (ref "J4") (pin "P5") (pinfunction "CLK_P5") (pintype "bidirectional"))
      (node (ref "R6") (pin "1") (pinfunction "1_1") (pintype "passive"))
      (node (ref "SCK") (pin "TP") (pinfunction "TP_TP") (pintype "input"))
      (node (ref "U1") (pin "6") (pinfunction "CLK_6") (pintype "input"))
      (node (ref "U2") (pin "6") (pinfunction "IO6_6") (pintype "bidirectional"))
    )
    (net (code "44") (name "SCL") (class "Default")
      (node (ref "J3") (pin "4") (pinfunction "4_4") (pintype "passive"))
      (node (ref "R2_PINH") (pin "1") (pinfunction "1_1") (pintype "passive"))
      (node (ref "SENSOR2") (pin "4") (pinfunction "SCK_4") (pintype "input"))
      (node (ref "U2") (pin "20") (pinfunction "IO22_20") (pintype "bidirectional"))
      (node (ref "U3") (pin "16") (pinfunction "SCL_16") (pintype "input"))
      (node (ref "U4") (pin "7") (pinfunction "SCL_7") (pintype "input"))
    )
    (net (code "45") (name "SDA") (class "Default")
      (node (ref "J3") (pin "3") (pinfunction "3_3") (pintype "passive"))
      (node (ref "R1_PINH") (pin "1") (pinfunction "1_1") (pintype "passive"))
      (node (ref "SENSOR2") (pin "3") (pinfunction "SDI_3") (pintype "bidirectional"))
      (node (ref "U2") (pin "19") (pinfunction "IO21_19") (pintype "bidirectional"))
      (node (ref "U3") (pin "15") (pinfunction "SDA_15") (pintype "bidirectional"))
      (node (ref "U4") (pin "8") (pinfunction "SDA_8") (pintype "bidirectional"))
    )
    (net (code "46") (name "SRC") (class "Default")
      (node (ref "C4") (pin "2") (pinfunction "2_2") (pintype "passive"))
      (node (ref "D5") (pin "2") (pinfunction "A_2") (pintype "bidirectional"))
      (node (ref "L1") (pin "1") (pinfunction "1_1") (pintype "passive"))
      (node (ref "Q3") (pin "3") (pinfunction "D_3") (pintype "bidirectional"))
    )
    (net (code "47") (name "SS_SD") (class "Default")
      (node (ref "D8") (pin "1") (pinfunction "1_1") (pintype "passive"))
      (node (ref "J4") (pin "P2") (pinfunction "CD/DAT3_P2") (pintype "bidirectional"))
      (node (ref "R10") (pin "1") (pinfunction "1_1") (pintype "passive"))
      (node (ref "U2") (pin "4") (pinfunction "IO4_4") (pintype "bidirectional"))
    )
    (net (code "48") (name "TX") (class "Default")
      (node (ref "TX") (pin "TP") (pinfunction "TP_TP") (pintype "input"))
      (node (ref "U2") (pin "25") (pinfunction "TXD0/GPIO16_25") (pintype "bidirectional"))
    )
    (net (code "49") (name "USB_D+") (class "Default")
      (node (ref "D1") (pin "1") (pinfunction "I/O1_1_1") (pintype "bidirectional"))
      (node (ref "U2") (pin "14") (pinfunction "IO13_14") (pintype "bidirectional"))
    )
    (net (code "50") (name "USB_D-") (class "Default")
      (node (ref "D1") (pin "3") (pinfunction "I/O2_1_3") (pintype "bidirectional"))
      (node (ref "U2") (pin "13") (pinfunction "IO12_13") (pintype "bidirectional"))
    )
    (net (code "51") (name "VBAT") (class "Default")
      (node (ref "C2_BAT") (pin "1") (pinfunction "1_1") (pintype "passive"))
      (node (ref "MCP73831") (pin "3") (pinfunction "VBAT_3") (pintype "power_in"))
      (node (ref "Q1") (pin "3") (pinfunction "D_3") (pintype "bidirectional"))
      (node (ref "TP3") (pin "TP") (pinfunction "TP_TP") (pintype "input"))
      (node (ref "U4") (pin "2") (pinfunction "CELL_2") (pintype "power_in"))
      (node (ref "U4") (pin "3") (pinfunction "VDD_3") (pintype "power_in"))
    )
    (net (code "52") (name "VBUS") (class "Default")
      (node (ref "C1_BAT") (pin "1") (pinfunction "1_1") (pintype "passive"))
      (node (ref "C4_USB") (pin "1") (pinfunction "1_1") (pintype "passive"))
      (node (ref "C5_USB") (pin "1") (pinfunction "1_1") (pintype "passive"))
      (node (ref "CHG_LED") (pin "A") (pinfunction "A_A") (pintype "passive"))
      (node (ref "D1") (pin "5") (pinfunction "VBUS_5") (pintype "bidirectional"))
      (node (ref "D2") (pin "2") (pinfunction "ANODE_2") (pintype "bidirectional"))
      (node (ref "MCP73831") (pin "4") (pinfunction "VIN_4") (pintype "power_in"))
      (node (ref "PFMF.050.1") (pin "2") (pinfunction "2_2") (pintype "passive"))
      (node (ref "Q1") (pin "1") (pinfunction "G_1") (pintype "bidirectional"))
      (node (ref "R1_PWRUSB") (pin "2") (pinfunction "2_2") (pintype "passive"))
      (node (ref "TP14") (pin "TP") (pinfunction "TP_TP") (pintype "input"))
    )
    (net (code "53") (name "VRTC") (class "Default")
      (node (ref "C10_SUPERCAP") (pin "2") (pinfunction "2_2") (pintype "passive"))
      (node (ref "C11") (pin "1") (pinfunction "1_1") (pintype "passive"))
      (node (ref "R_CAPACITOR") (pin "2") (pinfunction "2_2") (pintype "passive"))
      (node (ref "U3") (pin "14") (pinfunction "VBAT_14") (pintype "power_in"))
    )
    (net (code "54") (name "VUSB") (class "Default")
      (node (ref "J2") (pin "A4") (pinfunction "A4_A4") (pintype "bidirectional"))
      (node (ref "J2") (pin "A9") (pinfunction "A9_A9") (pintype "bidirectional"))
      (node (ref "J2") (pin "B4") (pinfunction "B4_B4") (pintype "bidirectional"))
      (node (ref "J2") (pin "B9") (pinfunction "B9_B9") (pintype "bidirectional"))
      (node (ref "PFMF.050.1") (pin "1") (pinfunction "1_1") (pintype "passive"))
    )
    (net (code "55") (name "unconnected-(IC1-NC-Pad4)") (class "Default")
      (node (ref "IC1") (pin "4") (pinfunction "NC_4") (pintype "no_connect"))
    )
    (net (code "56") (name "unconnected-(IC4-NC-Pad4)") (class "Default")
      (node (ref "IC4") (pin "4") (pinfunction "NC_4") (pintype "no_connect"))
    )
    (net (code "57") (name "unconnected-(J1-Pad1)") (class "Default")
      (node (ref "J1") (pin "1") (pinfunction "1_1") (pintype "bidirectional"))
    )
    (net (code "58") (name "unconnected-(J1-Pad6)") (class "Default")
      (node (ref "J1") (pin "6") (pinfunction "6_6") (pintype "bidirectional"))
    )
    (net (code "59") (name "unconnected-(J1-Pad7)") (class "Default")
      (node (ref "J1") (pin "7") (pinfunction "7_7") (pintype "bidirectional"))
    )
    (net (code "60") (name "unconnected-(J2-PadA8)") (class "Default")
      (node (ref "J2") (pin "A8") (pinfunction "A8_A8") (pintype "bidirectional"))
    )
    (net (code "61") (name "unconnected-(J2-PadB8)") (class "Default")
      (node (ref "J2") (pin "B8") (pinfunction "B8_B8") (pintype "bidirectional"))
    )
    (net (code "62") (name "unconnected-(J4-DAT1-PadP8)") (class "Default")
      (node (ref "J4") (pin "P8") (pinfunction "DAT1_P8") (pintype "bidirectional"))
    )
    (net (code "63") (name "unconnected-(J4-DAT2-PadP1)") (class "Default")
      (node (ref "J4") (pin "P1") (pinfunction "DAT2_P1") (pintype "bidirectional"))
    )
    (net (code "64") (name "unconnected-(J4-DETECTION_1-PadS1)") (class "Default")
      (node (ref "J4") (pin "S1") (pinfunction "DETECTION_1_S1") (pintype "bidirectional"))
    )
    (net (code "65") (name "unconnected-(J4-DETECTION_2-PadS2)") (class "Default")
      (node (ref "J4") (pin "S2") (pinfunction "DETECTION_2_S2") (pintype "bidirectional"))
    )
    (net (code "66") (name "unconnected-(Q1-S-Pad2)") (class "Default")
      (node (ref "Q1") (pin "2") (pinfunction "S_2") (pintype "bidirectional"))
    )
    (net (code "67") (name "unconnected-(U2-NC-Pad22)") (class "Default")
      (node (ref "U2") (pin "22") (pinfunction "NC_22") (pintype "no_connect"))
    )
    (net (code "68") (name "unconnected-(U4-~{ALERT}-Pad5)") (class "Default")
      (node (ref "U4") (pin "5") (pinfunction "~{ALERT}_5") (pintype "output"))
    )
  )
)
